# Power.net
KiCad netlist of a schematic drawn in Altium Designer
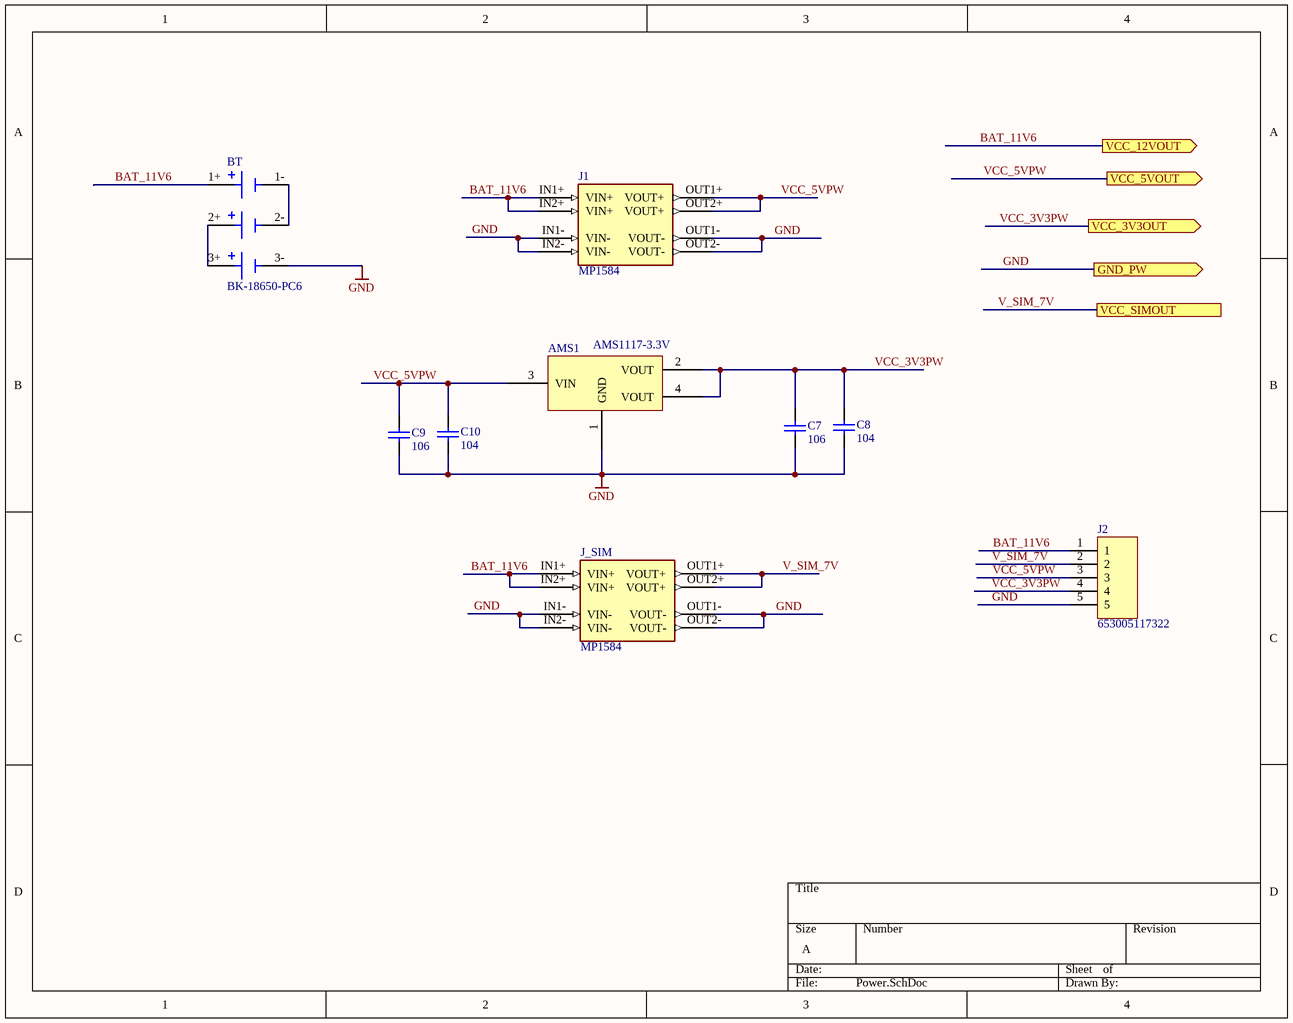
[diagram p0: Power.SchDoc]

(export (version "E")
  (design (tool "Eeschema 10.0.6"))
  (components
    (comp (ref "AMS1")
      (value "AMS1117-3.3V")
      (footprint "SOT223")
      (description "Dán")
      (libsource (lib "Altium_Lib_by_KhueNguyenCreator") (part "AMS1117 SMD"))
    )
    (comp (ref "BT")
      (value "BK-18650-PC6")
      (footprint "BAT_BK-18650-PC6")
      (description "Battery Holder _Open_ 18650 3 Cell PC Pin")
      (fields (field (name "MF") "MPD"))
      (libsource (lib "BK-18650-PC6") (part "BK-18650-PC6"))
    )
    (comp (ref "C7")
      (value "106")
      (footprint "tu 0805")
      (description "Dán")
      (libsource (lib "Altium_Lib_by_KhueNguyenCreator") (part "Tu 0805 106 16V 10%"))
    )
    (comp (ref "C8")
      (value "104")
      (footprint "tu 0805")
      (description "Dán")
      (libsource (lib "Altium_Lib_by_KhueNguyenCreator") (part "Tu 0805 104 50V 10%"))
    )
    (comp (ref "C9")
      (value "106")
      (footprint "tu 0805")
      (description "Dán")
      (libsource (lib "Altium_Lib_by_KhueNguyenCreator") (part "Tu 0805 106 16V 10%"))
    )
    (comp (ref "C10")
      (value "104")
      (footprint "tu 0805")
      (description "Dán")
      (libsource (lib "Altium_Lib_by_KhueNguyenCreator") (part "Tu 0805 104 50V 10%"))
    )
    (comp (ref "J1")
      (value "MP1584")
      (footprint "DC-BRICK")
      (fields (field (name "MF") "Monolithic Power"))
      (libsource (lib "MP1584") (part "MP1584"))
    )
    (comp (ref "J2")
      (value "653005117322")
      (footprint "CON5_50_653005117322_TH_RA")
      (description "5 Pins, 1 Row 1.25mm Pitch, right angle Connector, male")
      (fields (field (name "MANUFACTURER") "JST") (field (name "MATING PART NUMBER") "653005113322"))
      (libsource (lib "Altium_Lib_by_KhueNguyenCreator") (part "CON-PLG_5X1-50-RA-TH"))
    )
    (comp (ref "J_SIM")
      (value "MP1584")
      (footprint "DC-BRICK")
      (fields (field (name "MF") "Monolithic Power"))
      (libsource (lib "MP1584") (part "MP1584"))
    )
  )
  (nets
    (net (code "1") (name "/BAT_11V6") (class "Default")
      (node (ref "BT") (pin "1+") (pinfunction "1+_1+") (pintype "passive"))
      (node (ref "J1") (pin "IN1+") (pinfunction "VIN+_IN1+") (pintype "input"))
      (node (ref "J1") (pin "IN2+") (pinfunction "VIN+_IN2+") (pintype "input"))
      (node (ref "J2") (pin "1") (pinfunction "1_1") (pintype "passive"))
      (node (ref "J_SIM") (pin "IN1+") (pinfunction "VIN+_IN1+") (pintype "input"))
      (node (ref "J_SIM") (pin "IN2+") (pinfunction "VIN+_IN2+") (pintype "input"))
    )
    (net (code "2") (name "/VCC_3V3PW") (class "Default")
      (node (ref "AMS1") (pin "2") (pinfunction "VOUT_2") (pintype "passive"))
      (node (ref "AMS1") (pin "4") (pinfunction "VOUT_4") (pintype "passive"))
      (node (ref "C7") (pin "1") (pinfunction "1_1") (pintype "passive"))
      (node (ref "C8") (pin "1") (pinfunction "1_1") (pintype "passive"))
      (node (ref "J2") (pin "4") (pinfunction "4_4") (pintype "passive"))
    )
    (net (code "3") (name "/VCC_5VPW") (class "Default")
      (node (ref "AMS1") (pin "3") (pinfunction "VIN_3") (pintype "passive"))
      (node (ref "C10") (pin "1") (pinfunction "1_1") (pintype "passive"))
      (node (ref "C9") (pin "1") (pinfunction "1_1") (pintype "passive"))
      (node (ref "J1") (pin "OUT1+") (pinfunction "VOUT+_OUT1+") (pintype "output"))
      (node (ref "J1") (pin "OUT2+") (pinfunction "VOUT+_OUT2+") (pintype "output"))
      (node (ref "J2") (pin "3") (pinfunction "3_3") (pintype "passive"))
    )
    (net (code "4") (name "/V_SIM_7V") (class "Default")
      (node (ref "J2") (pin "2") (pinfunction "2_2") (pintype "passive"))
      (node (ref "J_SIM") (pin "OUT1+") (pinfunction "VOUT+_OUT1+") (pintype "output"))
      (node (ref "J_SIM") (pin "OUT2+") (pinfunction "VOUT+_OUT2+") (pintype "output"))
    )
    (net (code "5") (name "GND") (class "Default")
      (node (ref "AMS1") (pin "1") (pinfunction "GND_1") (pintype "passive"))
      (node (ref "BT") (pin "3-") (pinfunction "3-_3-") (pintype "passive"))
      (node (ref "C10") (pin "2") (pinfunction "2_2") (pintype "passive"))
      (node (ref "C7") (pin "2") (pinfunction "2_2") (pintype "passive"))
      (node (ref "C8") (pin "2") (pinfunction "2_2") (pintype "passive"))
      (node (ref "C9") (pin "2") (pinfunction "2_2") (pintype "passive"))
      (node (ref "J1") (pin "IN1-") (pinfunction "VIN-_IN1-") (pintype "input"))
      (node (ref "J1") (pin "IN2-") (pinfunction "VIN-_IN2-") (pintype "input"))
      (node (ref "J1") (pin "OUT1-") (pinfunction "VOUT-_OUT1-") (pintype "output"))
      (node (ref "J1") (pin "OUT2-") (pinfunction "VOUT-_OUT2-") (pintype "output"))
      (node (ref "J2") (pin "5") (pinfunction "5_5") (pintype "passive"))
      (node (ref "J_SIM") (pin "IN1-") (pinfunction "VIN-_IN1-") (pintype "input"))
      (node (ref "J_SIM") (pin "IN2-") (pinfunction "VIN-_IN2-") (pintype "input"))
      (node (ref "J_SIM") (pin "OUT1-") (pinfunction "VOUT-_OUT1-") (pintype "output"))
      (node (ref "J_SIM") (pin "OUT2-") (pinfunction "VOUT-_OUT2-") (pintype "output"))
    )
    (net (code "6") (name "Net-(BT-Pad1-)") (class "Default")
      (node (ref "BT") (pin "1-") (pinfunction "1-_1-") (pintype "passive"))
      (node (ref "BT") (pin "2-") (pinfunction "2-_2-") (pintype "passive"))
    )
    (net (code "7") (name "Net-(BT-Pad2+)") (class "Default")
      (node (ref "BT") (pin "2+") (pinfunction "2+_2+") (pintype "passive"))
      (node (ref "BT") (pin "3+") (pinfunction "3+_3+") (pintype "passive"))
    )
  )
)
